# Juice_Rescue_v2_-_hw1_0_2.net
KiCad netlist of a schematic drawn in EAGLE
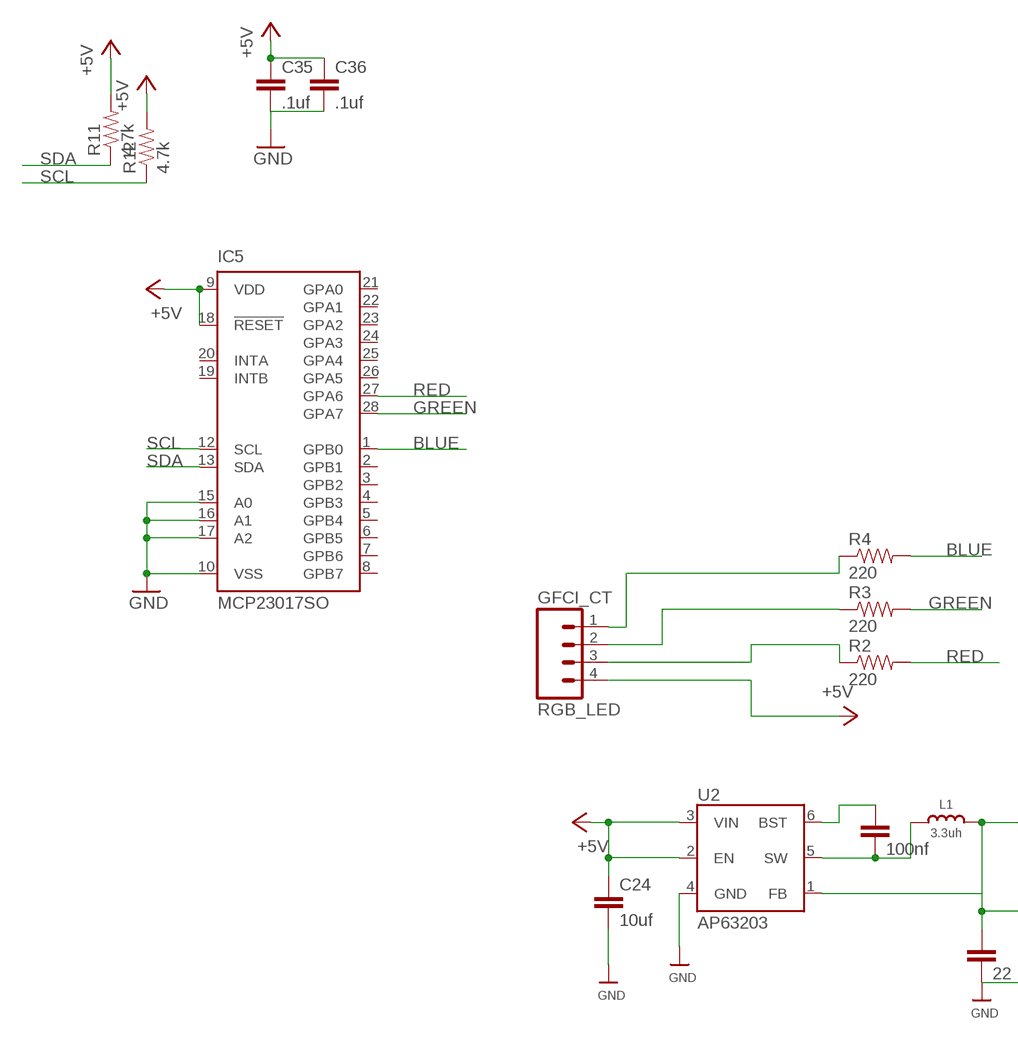
[diagram p0: schematic, sheet 1, part 1 of 2]
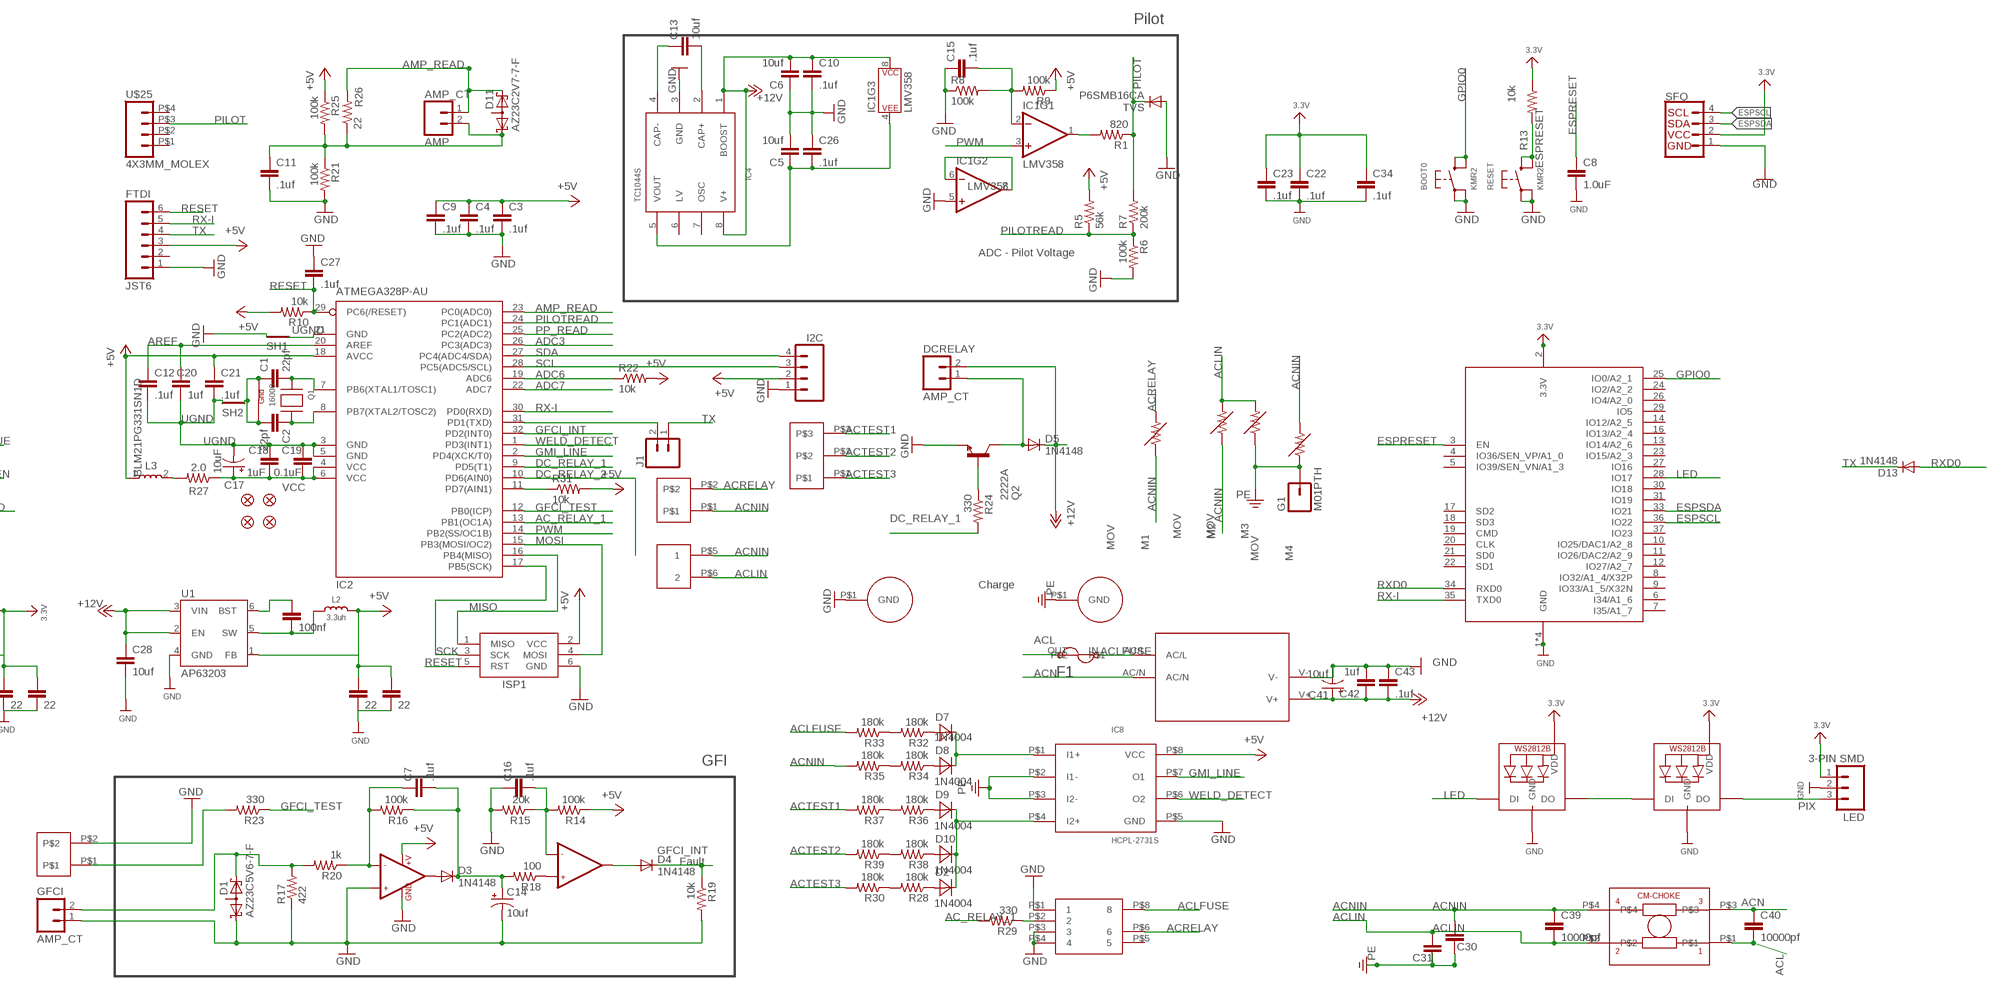
[diagram p1: schematic, sheet 1, part 2 of 2]

(export (version "E")
  (design (tool "Eeschema 10.0.6"))
  (components
    (comp (ref "AC")
      (value "2POS3.96MM")
      (footprint "eagle-import:2POS3.66MM")
      (libsource (lib "eagle-import") (part "2POS3.96MM"))
    )
    (comp (ref "AC_TEST")
      (value "AMPAC3P")
      (footprint "eagle-import:ACAMP3P")
      (libsource (lib "eagle-import") (part "AMPAC3P"))
    )
    (comp (ref "AMP")
      (value "AMP_CT")
      (footprint "eagle-import:MOLEX_2")
      (libsource (lib "eagle-import") (part "MOLEX_2"))
    )
    (comp (ref "BOOT0")
      (value "KMR2")
      (footprint "eagle-import:BTN_KMR2_4.6X2.8")
      (libsource (lib "eagle-import") (part "SWITCH_TACT_SMT4.6X2.8"))
    )
    (comp (ref "C1")
      (value "22pf")
      (footprint "eagle-import:0805")
      (libsource (lib "eagle-import") (part "CAP0805"))
    )
    (comp (ref "C2")
      (value "22pf")
      (footprint "eagle-import:0805")
      (libsource (lib "eagle-import") (part "CAP0805"))
    )
    (comp (ref "C3")
      (value ".1uf")
      (footprint "eagle-import:0805")
      (libsource (lib "eagle-import") (part "CAP0805"))
    )
    (comp (ref "C4")
      (value ".1uf")
      (footprint "eagle-import:0805")
      (libsource (lib "eagle-import") (part "CAP0805"))
    )
    (comp (ref "C5")
      (value "10uf")
      (footprint "eagle-import:0805")
      (libsource (lib "eagle-import") (part "CAP0805"))
    )
    (comp (ref "C6")
      (value "10uf")
      (footprint "eagle-import:0805")
      (libsource (lib "eagle-import") (part "CAP0805"))
    )
    (comp (ref "C7")
      (value ".1uf")
      (footprint "eagle-import:0805")
      (libsource (lib "eagle-import") (part "CAP0805"))
    )
    (comp (ref "C8")
      (value "1.0uF")
      (footprint "eagle-import:0805")
      (libsource (lib "eagle-import") (part "1.0UF-0805-25V-(+80/-20%)"))
    )
    (comp (ref "C9")
      (value ".1uf")
      (footprint "eagle-import:0805")
      (libsource (lib "eagle-import") (part "CAP0805"))
    )
    (comp (ref "C10")
      (value ".1uf")
      (footprint "eagle-import:0805")
      (libsource (lib "eagle-import") (part "CAP0805"))
    )
    (comp (ref "C11")
      (value ".1uf")
      (footprint "eagle-import:0805")
      (libsource (lib "eagle-import") (part "CAP0805"))
    )
    (comp (ref "C12")
      (value ".1uf")
      (footprint "eagle-import:0805")
      (libsource (lib "eagle-import") (part "CAP0805"))
    )
    (comp (ref "C13")
      (value "10uf")
      (footprint "eagle-import:0805")
      (libsource (lib "eagle-import") (part "CAP0805"))
    )
    (comp (ref "C14")
      (value "10uf")
      (footprint "eagle-import:EIA3216")
      (libsource (lib "eagle-import") (part "CAP_POL1206"))
    )
    (comp (ref "C15")
      (value ".1uf")
      (footprint "eagle-import:0805")
      (libsource (lib "eagle-import") (part "CAP0805"))
    )
    (comp (ref "C16")
      (value ".1uf")
      (footprint "eagle-import:0805")
      (libsource (lib "eagle-import") (part "CAP0805"))
    )
    (comp (ref "C17")
      (value "10uF")
      (footprint "eagle-import:0603-POLAR")
      (libsource (lib "eagle-import") (part "10UF-POLAR-0603-6.3V-20%(TANT)"))
    )
    (comp (ref "C18")
      (value "1uF")
      (footprint "eagle-import:0805")
      (libsource (lib "eagle-import") (part "CAP0805"))
    )
    (comp (ref "C19")
      (value "0.1uF")
      (footprint "eagle-import:0805")
      (libsource (lib "eagle-import") (part "CAP0805"))
    )
    (comp (ref "C20")
      (value "1uf")
      (footprint "eagle-import:0805")
      (libsource (lib "eagle-import") (part "CAP0805"))
    )
    (comp (ref "C21")
      (value ".1uf")
      (footprint "eagle-import:0805")
      (libsource (lib "eagle-import") (part "CAP0805"))
    )
    (comp (ref "C22")
      (value ".1uf")
      (footprint "eagle-import:0805")
      (libsource (lib "eagle-import") (part "1.0UF-0805-25V-(+80/-20%)"))
    )
    (comp (ref "C23")
      (value ".1uf")
      (footprint "eagle-import:0805")
      (libsource (lib "eagle-import") (part "1.0UF-0805-25V-(+80/-20%)"))
    )
    (comp (ref "C24")
      (value "10uf")
      (footprint "eagle-import:0805")
      (libsource (lib "eagle-import") (part "1.0UF-0805-25V-(+80/-20%)"))
    )
    (comp (ref "C25")
      (value "22")
      (footprint "eagle-import:0805")
      (libsource (lib "eagle-import") (part "1.0UF-0805-25V-(+80/-20%)"))
    )
    (comp (ref "C26")
      (value ".1uf")
      (footprint "eagle-import:0805")
      (libsource (lib "eagle-import") (part "CAP0805"))
    )
    (comp (ref "C27")
      (value ".1uf")
      (footprint "eagle-import:0805")
      (libsource (lib "eagle-import") (part "CAP0805"))
    )
    (comp (ref "C28")
      (value "10uf")
      (footprint "eagle-import:0805")
      (libsource (lib "eagle-import") (part "1.0UF-0805-25V-(+80/-20%)"))
    )
    (comp (ref "C29")
      (value "22")
      (footprint "eagle-import:0805")
      (libsource (lib "eagle-import") (part "1.0UF-0805-25V-(+80/-20%)"))
    )
    (comp (ref "C30")
      (value "100nf")
      (footprint "eagle-import:0805")
      (libsource (lib "eagle-import") (part "1.0UF-0805-25V-(+80/-20%)"))
    )
    (comp (ref "C31")
      (value "22")
      (footprint "eagle-import:0805")
      (libsource (lib "eagle-import") (part "1.0UF-0805-25V-(+80/-20%)"))
    )
    (comp (ref "C32")
      (value "100nf")
      (footprint "eagle-import:0805")
      (libsource (lib "eagle-import") (part "1.0UF-0805-25V-(+80/-20%)"))
    )
    (comp (ref "C33")
      (value "22")
      (footprint "eagle-import:0805")
      (libsource (lib "eagle-import") (part "1.0UF-0805-25V-(+80/-20%)"))
    )
    (comp (ref "C34")
      (value ".1uf")
      (footprint "eagle-import:0805")
      (libsource (lib "eagle-import") (part "1.0UF-0805-25V-(+80/-20%)"))
    )
    (comp (ref "C35")
      (value ".1uf")
      (footprint "eagle-import:0805")
      (libsource (lib "eagle-import") (part "CAP0805"))
    )
    (comp (ref "C36")
      (value ".1uf")
      (footprint "eagle-import:0805")
      (libsource (lib "eagle-import") (part "CAP0805"))
    )
    (comp (ref "C37")
      (value "1000pf")
      (footprint "eagle-import:DK1E3EA")
      (libsource (lib "eagle-import") (part "DK1"))
    )
    (comp (ref "C39")
      (value "10000pf")
      (footprint "eagle-import:C7.5B4")
      (libsource (lib "eagle-import") (part "C7.5/4"))
    )
    (comp (ref "C40")
      (value "10000pf")
      (footprint "eagle-import:C7.5B4")
      (libsource (lib "eagle-import") (part "C7.5/4"))
    )
    (comp (ref "C41")
      (value "10uf")
      (footprint "eagle-import:EIA3216")
      (libsource (lib "eagle-import") (part "CAP_POL1206"))
    )
    (comp (ref "C42")
      (value "1uf")
      (footprint "eagle-import:0805")
      (libsource (lib "eagle-import") (part "CAP0805"))
    )
    (comp (ref "C43")
      (value ".1uf")
      (footprint "eagle-import:0805")
      (libsource (lib "eagle-import") (part "CAP0805"))
    )
    (comp (ref "CMC")
      (value "RN214-0.3-02-47M")
      (footprint "eagle-import:RN214-0.3-02-47M")
      (libsource (lib "eagle-import") (part "RN214-0.3-02-47M"))
    )
    (comp (ref "D1")
      (value "AZ23C5V6-7-F")
      (footprint "eagle-import:SOT23")
      (libsource (lib "eagle-import") (part "BAS40-06"))
    )
    (comp (ref "D2")
      (value "1N4004")
      (footprint "eagle-import:SMA")
      (libsource (lib "eagle-import") (part "MBRA340T3"))
    )
    (comp (ref "D3")
      (value "1N4148")
      (footprint "eagle-import:SOD123")
      (libsource (lib "eagle-import") (part "DIODE-SOD123"))
    )
    (comp (ref "D4")
      (value "1N4148")
      (footprint "eagle-import:SOD123")
      (libsource (lib "eagle-import") (part "DIODE-SOD123"))
    )
    (comp (ref "D5")
      (value "1N4148")
      (footprint "eagle-import:SOD123")
      (libsource (lib "eagle-import") (part "DIODE-SOD123"))
    )
    (comp (ref "D7")
      (value "1N4004")
      (footprint "eagle-import:SMA")
      (libsource (lib "eagle-import") (part "MBRA340T3"))
    )
    (comp (ref "D8")
      (value "1N4004")
      (footprint "eagle-import:SMA")
      (libsource (lib "eagle-import") (part "MBRA340T3"))
    )
    (comp (ref "D9")
      (value "1N4004")
      (footprint "eagle-import:SMA")
      (libsource (lib "eagle-import") (part "MBRA340T3"))
    )
    (comp (ref "D10")
      (value "1N4004")
      (footprint "eagle-import:SMA")
      (libsource (lib "eagle-import") (part "MBRA340T3"))
    )
    (comp (ref "D11")
      (value "AZ23C2V7-7-F")
      (footprint "eagle-import:SOT23")
      (libsource (lib "eagle-import") (part "BAS40-06"))
    )
    (comp (ref "D13")
      (value "1N4148")
      (footprint "eagle-import:SOD123")
      (libsource (lib "eagle-import") (part "DIODE-SOD123"))
    )
    (comp (ref "DCRELAY")
      (value "AMP_CT")
      (footprint "eagle-import:MOLEX_2")
      (libsource (lib "eagle-import") (part "MOLEX_2"))
    )
    (comp (ref "F1")
      (value "BEL1.6AFUSE")
      (footprint "eagle-import:BELFUSE1A")
      (libsource (lib "eagle-import") (part "BEL1AFUSE"))
    )
    (comp (ref "FID1")
      (value "FIDUCIAL1X2.5")
      (footprint "eagle-import:FIDUCIAL-1X2.5")
      (libsource (lib "eagle-import") (part "FIDUCIAL1X2.5"))
    )
    (comp (ref "FID2")
      (value "FIDUCIAL1X2.5")
      (footprint "eagle-import:FIDUCIAL-1X2.5")
      (libsource (lib "eagle-import") (part "FIDUCIAL1X2.5"))
    )
    (comp (ref "FID3")
      (value "FIDUCIAL1X2.5")
      (footprint "eagle-import:FIDUCIAL-1X2.5")
      (libsource (lib "eagle-import") (part "FIDUCIAL1X2.5"))
    )
    (comp (ref "FID4")
      (value "FIDUCIAL1X2.5")
      (footprint "eagle-import:FIDUCIAL-1X2.5")
      (libsource (lib "eagle-import") (part "FIDUCIAL1X2.5"))
    )
    (comp (ref "FTDI")
      (value "JST6")
      (footprint "eagle-import:JST6")
      (libsource (lib "eagle-import") (part "JST6"))
    )
    (comp (ref "G1")
      (value "M01PTH")
      (footprint "eagle-import:1X01")
      (libsource (lib "eagle-import") (part "M01PTH"))
    )
    (comp (ref "GFCI")
      (value "AMP_CT")
      (footprint "eagle-import:MOLEX_2")
      (libsource (lib "eagle-import") (part "MOLEX_2"))
    )
    (comp (ref "I2C")
      (value "M04JST-PTH-VERT")
      (footprint "eagle-import:JST-4-PTH-VERT")
      (libsource (lib "eagle-import") (part "M04JST-PTH-VERT"))
    )
    (comp (ref "IC1")
      (value "LMV358")
      (footprint "eagle-import:SO08")
      (libsource (lib "eagle-import") (part "LMV358SOIC"))
    )
    (comp (ref "IC2")
      (value "ATMEGA328P-AU")
      (footprint "eagle-import:TQFP32-08")
      (fields (field (name "MPN") "ATMEGA8-16AU"))
      (libsource (lib "eagle-import") (part "MEGA8-AI"))
    )
    (comp (ref "IC3")
      (value "LM358")
      (footprint "eagle-import:SO08")
      (libsource (lib "eagle-import") (part "LMV358"))
    )
    (comp (ref "IC4")
      (value "TC1044S")
      (footprint "eagle-import:SO-8")
      (libsource (lib "eagle-import") (part "TC1044S"))
    )
    (comp (ref "IC5")
      (value "MCP23017SO")
      (footprint "eagle-import:SO28W")
      (libsource (lib "eagle-import") (part "MCP23017SO"))
    )
    (comp (ref "IC7")
      (value "AQH2223")
      (footprint "eagle-import:SIL8")
      (libsource (lib "eagle-import") (part "AQH2223"))
    )
    (comp (ref "IC8")
      (value "HCPL-2731S")
      (footprint "eagle-import:SIL8-2")
      (libsource (lib "eagle-import") (part "HCPL-2731S"))
    )
    (comp (ref "ISP1")
      (value "ISP1")
      (footprint "eagle-import:AVRISP")
      (libsource (lib "eagle-import") (part "AVRISP-6"))
    )
    (comp (ref "J1")
      (value "CONN_02")
      (footprint "eagle-import:1X02")
      (libsource (lib "eagle-import") (part "CONN_02"))
    )
    (comp (ref "L1")
      (value "3.3uh")
      (footprint "eagle-import:MICROBUILDER_INDUCTOR_5X5MM_NR5040_NOTHERMALS")
      (libsource (lib "eagle-import") (part "MICROBUILDER_INDUCTORNR5040"))
    )
    (comp (ref "L2")
      (value "3.3uh")
      (footprint "eagle-import:MICROBUILDER_INDUCTOR_5X5MM_NR5040_NOTHERMALS")
      (libsource (lib "eagle-import") (part "MICROBUILDER_INDUCTORNR5040"))
    )
    (comp (ref "L3")
      (value "BLM21PG331SN1D")
      (footprint "eagle-import:INDC2012X87")
      (fields (field (name "MF") "Murata"))
      (libsource (lib "eagle-import") (part "BLM21PG331SN1D"))
    )
    (comp (ref "LED")
      (value "3-PIN SMD")
      (footprint "eagle-import:JST-3-SMD")
      (libsource (lib "eagle-import") (part "M03JST-SMD"))
    )
    (comp (ref "LED1")
      (value "WS2812B3535")
      (footprint "eagle-import:LED3535")
      (libsource (lib "eagle-import") (part "WS2812B3535"))
    )
    (comp (ref "LED2")
      (value "WS2812B3535")
      (footprint "eagle-import:LED3535")
      (libsource (lib "eagle-import") (part "WS2812B3535"))
    )
    (comp (ref "M1")
      (value "MOV")
      (footprint "eagle-import:MOV")
      (libsource (lib "eagle-import") (part "MOV"))
    )
    (comp (ref "M2")
      (value "MOV")
      (footprint "eagle-import:MOV")
      (libsource (lib "eagle-import") (part "MOV"))
    )
    (comp (ref "M3")
      (value "MOV")
      (footprint "eagle-import:MOV")
      (libsource (lib "eagle-import") (part "MOV"))
    )
    (comp (ref "M4")
      (value "MOV")
      (footprint "eagle-import:MOV")
      (libsource (lib "eagle-import") (part "MOV"))
    )
    (comp (ref "PS1")
      (value "IRM-10-5")
      (footprint "eagle-import:IRM-10-5")
      (libsource (lib "eagle-import") (part "IRM-10-5"))
    )
    (comp (ref "Q1")
      (value "16000")
      (footprint "eagle-import:NX3225")
      (libsource (lib "eagle-import") (part "XTAL-4-3225"))
    )
    (comp (ref "Q2")
      (value "2222A")
      (footprint "eagle-import:SOT23")
      (libsource (lib "eagle-import") (part "BCX70SMD"))
    )
    (comp (ref "R1")
      (value "820")
      (footprint "eagle-import:0805")
      (libsource (lib "eagle-import") (part "RESISTOR0805-RES"))
    )
    (comp (ref "R2")
      (value "220")
      (footprint "eagle-import:0805")
      (libsource (lib "eagle-import") (part "RESISTOR0805-RES"))
    )
    (comp (ref "R3")
      (value "220")
      (footprint "eagle-import:0805")
      (libsource (lib "eagle-import") (part "RESISTOR0805-RES"))
    )
    (comp (ref "R4")
      (value "220")
      (footprint "eagle-import:0805")
      (libsource (lib "eagle-import") (part "RESISTOR0805-RES"))
    )
    (comp (ref "R5")
      (value "56k")
      (footprint "eagle-import:0805")
      (libsource (lib "eagle-import") (part "RESISTOR0805-RES"))
    )
    (comp (ref "R6")
      (value "100k")
      (footprint "eagle-import:0805")
      (libsource (lib "eagle-import") (part "RESISTOR0805-RES"))
    )
    (comp (ref "R7")
      (value "200k")
      (footprint "eagle-import:0805")
      (libsource (lib "eagle-import") (part "RESISTOR0805-RES"))
    )
    (comp (ref "R8")
      (value "100k")
      (footprint "eagle-import:0805")
      (libsource (lib "eagle-import") (part "RESISTOR0805-RES"))
    )
    (comp (ref "R9")
      (value "100k")
      (footprint "eagle-import:0805")
      (libsource (lib "eagle-import") (part "RESISTOR0805-RES"))
    )
    (comp (ref "R10")
      (value "10k")
      (footprint "eagle-import:0805")
      (libsource (lib "eagle-import") (part "RESISTOR0805-RES"))
    )
    (comp (ref "R11")
      (value "4.7k")
      (footprint "eagle-import:0805")
      (libsource (lib "eagle-import") (part "RESISTOR0805-RES"))
    )
    (comp (ref "R12")
      (value "4.7k")
      (footprint "eagle-import:0805")
      (libsource (lib "eagle-import") (part "RESISTOR0805-RES"))
    )
    (comp (ref "R13")
      (value "10k")
      (footprint "eagle-import:0805")
      (libsource (lib "eagle-import") (part "RESISTOR0805"))
    )
    (comp (ref "R14")
      (value "100k")
      (footprint "eagle-import:0805")
      (libsource (lib "eagle-import") (part "RESISTOR0805-RES"))
    )
    (comp (ref "R15")
      (value "20k")
      (footprint "eagle-import:0805")
      (libsource (lib "eagle-import") (part "RESISTOR0805-RES"))
    )
    (comp (ref "R16")
      (value "100k")
      (footprint "eagle-import:0805")
      (libsource (lib "eagle-import") (part "RESISTOR0805-RES"))
    )
    (comp (ref "R17")
      (value "422")
      (footprint "eagle-import:0805")
      (libsource (lib "eagle-import") (part "RESISTOR0805-RES"))
    )
    (comp (ref "R18")
      (value "100")
      (footprint "eagle-import:0805")
      (libsource (lib "eagle-import") (part "RESISTOR0805-RES"))
    )
    (comp (ref "R19")
      (value "10k")
      (footprint "eagle-import:0805")
      (libsource (lib "eagle-import") (part "RESISTOR0805-RES"))
    )
    (comp (ref "R20")
      (value "1k")
      (footprint "eagle-import:0805")
      (libsource (lib "eagle-import") (part "RESISTOR0805-RES"))
    )
    (comp (ref "R21")
      (value "100k")
      (footprint "eagle-import:0805")
      (libsource (lib "eagle-import") (part "RESISTOR0805-RES"))
    )
    (comp (ref "R22")
      (value "10k")
      (footprint "eagle-import:0805")
      (libsource (lib "eagle-import") (part "RESISTOR0805-RES"))
    )
    (comp (ref "R23")
      (value "330")
      (footprint "eagle-import:0805")
      (libsource (lib "eagle-import") (part "RESISTOR0805-RES"))
    )
    (comp (ref "R24")
      (value "330")
      (footprint "eagle-import:0805")
      (libsource (lib "eagle-import") (part "RESISTOR0805-RES"))
    )
    (comp (ref "R25")
      (value "100k")
      (footprint "eagle-import:0805")
      (libsource (lib "eagle-import") (part "RESISTOR0805-RES"))
    )
    (comp (ref "R26")
      (value "22")
      (footprint "eagle-import:R1206")
      (libsource (lib "eagle-import") (part "R-US_R1206"))
    )
    (comp (ref "R27")
      (value "2.0")
      (footprint "eagle-import:0805")
      (libsource (lib "eagle-import") (part "RESISTOR0805-RES"))
    )
    (comp (ref "R28")
      (value "180k")
      (footprint "eagle-import:1210")
      (libsource (lib "eagle-import") (part "0.1OHM-1/2W-1%(1210)"))
    )
    (comp (ref "R29")
      (value "330")
      (footprint "eagle-import:0805")
      (libsource (lib "eagle-import") (part "RESISTOR0805-RES"))
    )
    (comp (ref "R30")
      (value "180k")
      (footprint "eagle-import:1210")
      (libsource (lib "eagle-import") (part "0.1OHM-1/2W-1%(1210)"))
    )
    (comp (ref "R31")
      (value "10k")
      (footprint "eagle-import:0805")
      (libsource (lib "eagle-import") (part "RESISTOR0805-RES"))
    )
    (comp (ref "R32")
      (value "180k")
      (footprint "eagle-import:1210")
      (libsource (lib "eagle-import") (part "0.1OHM-1/2W-1%(1210)"))
    )
    (comp (ref "R33")
      (value "180k")
      (footprint "eagle-import:1210")
      (libsource (lib "eagle-import") (part "0.1OHM-1/2W-1%(1210)"))
    )
    (comp (ref "R34")
      (value "180k")
      (footprint "eagle-import:1210")
      (libsource (lib "eagle-import") (part "0.1OHM-1/2W-1%(1210)"))
    )
    (comp (ref "R35")
      (value "180k")
      (footprint "eagle-import:1210")
      (libsource (lib "eagle-import") (part "0.1OHM-1/2W-1%(1210)"))
    )
    (comp (ref "R36")
      (value "180k")
      (footprint "eagle-import:1210")
      (libsource (lib "eagle-import") (part "0.1OHM-1/2W-1%(1210)"))
    )
    (comp (ref "R37")
      (value "180k")
      (footprint "eagle-import:1210")
      (libsource (lib "eagle-import") (part "0.1OHM-1/2W-1%(1210)"))
    )
    (comp (ref "R38")
      (value "180k")
      (footprint "eagle-import:1210")
      (libsource (lib "eagle-import") (part "0.1OHM-1/2W-1%(1210)"))
    )
    (comp (ref "R39")
      (value "180k")
      (footprint "eagle-import:1210")
      (libsource (lib "eagle-import") (part "0.1OHM-1/2W-1%(1210)"))
    )
    (comp (ref "RESET")
      (value "KMR2")
      (footprint "eagle-import:BTN_KMR2_4.6X2.8")
      (libsource (lib "eagle-import") (part "SWITCH_TACT_SMT4.6X2.8"))
    )
    (comp (ref "RF1")
      (value "1000pf")
      (footprint "eagle-import:DK1E3EA")
      (libsource (lib "eagle-import") (part "DK1"))
    )
    (comp (ref "RGB_LED")
      (value "GFCI_CT")
      (footprint "eagle-import:GFCI_4")
      (libsource (lib "eagle-import") (part "GFCI_4"))
    )
    (comp (ref "SFQ")
      (value "QWIIC_CONNECTORJS-1MM")
      (footprint "eagle-import:JST04_1MM_RA")
      (libsource (lib "eagle-import") (part "QWIIC_CONNECTORJS-1MM"))
    )
    (comp (ref "SH1")
      (value "SHORT-HT5")
      (footprint "eagle-import:SHORT_TOP-50")
      (libsource (lib "eagle-import") (part "SHORT-HT5"))
    )
    (comp (ref "SH2")
      (value "SHORT-HT5")
      (footprint "eagle-import:SHORT_TOP-50")
      (libsource (lib "eagle-import") (part "SHORT-HT5"))
    )
    (comp (ref "TEST_COIL")
      (value "2X4MM")
      (footprint "eagle-import:2X4MM")
      (libsource (lib "eagle-import") (part "2X4MM"))
    )
    (comp (ref "TVS")
      (value "P6SMB16CA")
      (footprint "eagle-import:SMB")
      (libsource (lib "eagle-import") (part "DIODE-SMB"))
    )
    (comp (ref "U$3")
      (value "HOLE")
      (footprint "eagle-import:HOLE")
      (libsource (lib "eagle-import") (part "HOLE"))
    )
    (comp (ref "U$8")
      (value "AMPAC")
      (footprint "eagle-import:AMPAC")
      (libsource (lib "eagle-import") (part "AMPAC"))
    )
    (comp (ref "U$9")
      (value "HOLE")
      (footprint "eagle-import:HOLE")
      (libsource (lib "eagle-import") (part "HOLE"))
    )
    (comp (ref "U$25")
      (value "4X3MM_MOLEX")
      (footprint "eagle-import:4X3MM_MOLEX")
      (libsource (lib "eagle-import") (part "4X3MM_MOLEX"))
    )
    (comp (ref "U1")
      (value "AP63203")
      (footprint "eagle-import:SOT23-6")
      (libsource (lib "eagle-import") (part "AP63203"))
    )
    (comp (ref "U2")
      (value "AP63203")
      (footprint "eagle-import:SOT23-6")
      (libsource (lib "eagle-import") (part "AP63203"))
    )
    (comp (ref "X2")
      (value "ESP32-WROOM-32")
      (footprint "eagle-import:WROOM32_SKINNY")
      (libsource (lib "eagle-import") (part "ESP32_WROOM32_SKINNY"))
    )
  )
  (nets
    (net (code "1") (name "+5V") (class "Default")
      (node (ref "C21") (pin "1") (pinfunction "1_1") (pintype "passive"))
      (node (ref "C24") (pin "1") (pinfunction "1_1") (pintype "passive"))
      (node (ref "C29") (pin "1") (pinfunction "1_1") (pintype "passive"))
      (node (ref "C3") (pin "1") (pinfunction "1_1") (pintype "passive"))
      (node (ref "C33") (pin "1") (pinfunction "1_1") (pintype "passive"))
      (node (ref "C35") (pin "1") (pinfunction "1_1") (pintype "passive"))
      (node (ref "C36") (pin "1") (pinfunction "1_1") (pintype "passive"))
      (node (ref "C4") (pin "1") (pinfunction "1_1") (pintype "passive"))
      (node (ref "C9") (pin "1") (pinfunction "1_1") (pintype "passive"))
      (node (ref "FTDI") (pin "3") (pinfunction "3_3") (pintype "passive"))
      (node (ref "I2C") (pin "2") (pinfunction "2_2") (pintype "passive"))
      (node (ref "IC2") (pin "18") (pinfunction "AVCC_18") (pintype "power_in"))
      (node (ref "IC3") (pin "8") (pinfunction "+V_8") (pintype "power_in"))
      (node (ref "IC5") (pin "18") (pinfunction "~{RESET}_18") (pintype "input"))
      (node (ref "IC5") (pin "9") (pinfunction "VDD_9") (pintype "power_in"))
      (node (ref "IC8") (pin "P$8") (pinfunction "VCC_P$8") (pintype "bidirectional"))
      (node (ref "ISP1") (pin "2") (pinfunction "VCC_2") (pintype "power_in"))
      (node (ref "L2") (pin "P$2") (pinfunction "2_P$2") (pintype "passive"))
      (node (ref "L3") (pin "1") (pinfunction "1_1") (pintype "passive"))
      (node (ref "R10") (pin "2") (pinfunction "2_2") (pintype "passive"))
      (node (ref "R11") (pin "2") (pinfunction "2_2") (pintype "passive"))
      (node (ref "R12") (pin "2") (pinfunction "2_2") (pintype "passive"))
      (node (ref "R14") (pin "1") (pinfunction "1_1") (pintype "passive"))
      (node (ref "R22") (pin "2") (pinfunction "2_2") (pintype "passive"))
      (node (ref "R25") (pin "1") (pinfunction "1_1") (pintype "passive"))
      (node (ref "R31") (pin "2") (pinfunction "2_2") (pintype "passive"))
      (node (ref "R5") (pin "2") (pinfunction "2_2") (pintype "passive"))
      (node (ref "R9") (pin "1") (pinfunction "1_1") (pintype "passive"))
      (node (ref "RGB_LED") (pin "4") (pinfunction "4_4") (pintype "passive"))
      (node (ref "U1") (pin "1") (pinfunction "FB_1") (pintype "bidirectional"))
      (node (ref "U2") (pin "2") (pinfunction "EN_2") (pintype "bidirectional"))
      (node (ref "U2") (pin "3") (pinfunction "VIN_3") (pintype "bidirectional"))
    )
    (net (code "2") (name "+12V") (class "Default")
      (node (ref "C10") (pin "1") (pinfunction "1_1") (pintype "passive"))
      (node (ref "C28") (pin "1") (pinfunction "1_1") (pintype "passive"))
      (node (ref "C41") (pin "A") (pinfunction "+_A") (pintype "passive"))
      (node (ref "C42") (pin "1") (pinfunction "1_1") (pintype "passive"))
      (node (ref "C43") (pin "2") (pinfunction "2_2") (pintype "passive"))
      (node (ref "C6") (pin "2") (pinfunction "2_2") (pintype "passive"))
      (node (ref "D5") (pin "C") (pinfunction "C_C") (pintype "passive"))
      (node (ref "DCRELAY") (pin "2") (pinfunction "2_2") (pintype "passive"))
      (node (ref "IC1") (pin "8") (pinfunction "P$V+_8") (pintype "bidirectional"))
      (node (ref "IC4") (pin "1") (pinfunction "BOOST_1") (pintype "bidirectional"))
      (node (ref "IC4") (pin "8") (pinfunction "V+_8") (pintype "bidirectional"))
      (node (ref "PS1") (pin "V+") (pinfunction "V+_V+") (pintype "bidirectional"))
      (node (ref "U1") (pin "2") (pinfunction "EN_2") (pintype "bidirectional"))
      (node (ref "U1") (pin "3") (pinfunction "VIN_3") (pintype "bidirectional"))
    )
    (net (code "3") (name "/ACL") (class "Default")
      (node (ref "C40") (pin "2") (pinfunction "2_2") (pintype "passive"))
      (node (ref "CMC") (pin "P$1") (pinfunction "P$1_P$1") (pintype "bidirectional"))
      (node (ref "F1") (pin "OUT") (pinfunction "P$1_OUT") (pintype "bidirectional"))
    )
    (net (code "4") (name "/ACLFUSE") (class "Default")
      (node (ref "F1") (pin "IN") (pinfunction "P$2_IN") (pintype "bidirectional"))
      (node (ref "IC7") (pin "P$8") (pinfunction "8_P$8") (pintype "bidirectional"))
      (node (ref "PS1") (pin "AC/L") (pinfunction "AC/L_AC/L") (pintype "bidirectional"))
      (node (ref "R33") (pin "2") (pinfunction "2_2") (pintype "passive"))
    )
    (net (code "5") (name "/ACLIN") (class "Default")
      (node (ref "AC") (pin "P$6") (pinfunction "2_P$6") (pintype "bidirectional"))
      (node (ref "C39") (pin "2") (pinfunction "2_2") (pintype "passive"))
      (node (ref "CMC") (pin "P$2") (pinfunction "P$2_P$2") (pintype "bidirectional"))
      (node (ref "M2") (pin "P$2") (pinfunction "2_P$2") (pintype "passive"))
      (node (ref "M3") (pin "P$2") (pinfunction "2_P$2") (pintype "passive"))
      (node (ref "RF1") (pin "P$2") (pinfunction "2_P$2") (pintype "passive"))
    )
    (net (code "6") (name "/ACN") (class "Default")
      (node (ref "C40") (pin "1") (pinfunction "1_1") (pintype "passive"))
      (node (ref "CMC") (pin "P$3") (pinfunction "P$3_P$3") (pintype "bidirectional"))
      (node (ref "PS1") (pin "AC/N") (pinfunction "AC/N_AC/N") (pintype "bidirectional"))
    )
    (net (code "7") (name "/ACNIN") (class "Default")
      (node (ref "AC") (pin "P$5") (pinfunction "1_P$5") (pintype "bidirectional"))
      (node (ref "C37") (pin "P$2") (pinfunction "2_P$2") (pintype "passive"))
      (node (ref "C39") (pin "1") (pinfunction "1_1") (pintype "passive"))
      (node (ref "CMC") (pin "P$4") (pinfunction "P$4_P$4") (pintype "bidirectional"))
      (node (ref "M1") (pin "P$1") (pinfunction "1_P$1") (pintype "passive"))
      (node (ref "M2") (pin "P$1") (pinfunction "1_P$1") (pintype "passive"))
      (node (ref "M4") (pin "P$2") (pinfunction "2_P$2") (pintype "passive"))
      (node (ref "R35") (pin "2") (pinfunction "2_2") (pintype "passive"))
      (node (ref "U$8") (pin "P$1") (pinfunction "P$1_P$1") (pintype "bidirectional"))
    )
    (net (code "8") (name "/ACRELAY") (class "Default")
      (node (ref "IC7") (pin "P$6") (pinfunction "6_P$6") (pintype "bidirectional"))
      (node (ref "M1") (pin "P$2") (pinfunction "2_P$2") (pintype "passive"))
      (node (ref "U$8") (pin "P$2") (pinfunction "P$2_P$2") (pintype "bidirectional"))
    )
    (net (code "9") (name "/ACTEST1") (class "Default")
      (node (ref "AC_TEST") (pin "P$3") (pinfunction "P$3_P$3") (pintype "bidirectional"))
      (node (ref "R37") (pin "2") (pinfunction "2_2") (pintype "passive"))
    )
    (net (code "10") (name "/ACTEST2") (class "Default")
      (node (ref "AC_TEST") (pin "P$2") (pinfunction "P$2_P$2") (pintype "bidirectional"))
      (node (ref "R39") (pin "2") (pinfunction "2_2") (pintype "passive"))
    )
    (net (code "11") (name "/ACTEST3") (class "Default")
      (node (ref "AC_TEST") (pin "P$1") (pinfunction "P$1_P$1") (pintype "bidirectional"))
      (node (ref "R30") (pin "2") (pinfunction "2_2") (pintype "passive"))
    )
    (net (code "12") (name "/AC_RELAY_1") (class "Default")
      (node (ref "IC2") (pin "13") (pinfunction "PB1(OC1A)_13") (pintype "bidirectional"))
      (node (ref "R29") (pin "2") (pinfunction "2_2") (pintype "passive"))
    )
    (net (code "13") (name "/ADC3") (class "Default")
      (node (ref "IC2") (pin "26") (pinfunction "PC3(ADC3)_26") (pintype "bidirectional"))
    )
    (net (code "14") (name "/ADC6") (class "Default")
      (node (ref "IC2") (pin "19") (pinfunction "ADC6_19") (pintype "bidirectional"))
      (node (ref "R22") (pin "1") (pinfunction "1_1") (pintype "passive"))
    )
    (net (code "15") (name "/ADC7") (class "Default")
      (node (ref "IC2") (pin "22") (pinfunction "ADC7_22") (pintype "bidirectional"))
    )
    (net (code "16") (name "/AMP_READ") (class "Default")
      (node (ref "AMP") (pin "1") (pinfunction "1_1") (pintype "passive"))
      (node (ref "D11") (pin "2") (pinfunction "K2_2") (pintype "passive"))
      (node (ref "IC2") (pin "23") (pinfunction "PC0(ADC0)_23") (pintype "bidirectional"))
      (node (ref "R26") (pin "2") (pinfunction "2_2") (pintype "passive"))
    )
    (net (code "17") (name "/AREF") (class "Default")
      (node (ref "C12") (pin "1") (pinfunction "1_1") (pintype "passive"))
      (node (ref "C20") (pin "1") (pinfunction "1_1") (pintype "passive"))
      (node (ref "IC2") (pin "20") (pinfunction "AREF_20") (pintype "passive"))
    )
    (net (code "18") (name "/BLUE") (class "Default")
      (node (ref "IC5") (pin "1") (pinfunction "GPB0_1") (pintype "bidirectional"))
      (node (ref "R4") (pin "2") (pinfunction "2_2") (pintype "passive"))
    )
    (net (code "19") (name "/DC_RELAY_1") (class "Default")
      (node (ref "IC2") (pin "9") (pinfunction "PD5(T1)_9") (pintype "bidirectional"))
      (node (ref "R24") (pin "2") (pinfunction "2_2") (pintype "passive"))
    )
    (net (code "20") (name "/DC_RELAY_2") (class "Default")
      (node (ref "IC2") (pin "10") (pinfunction "PD6(AIN0)_10") (pintype "bidirectional"))
    )
    (net (code "21") (name "/ESPRESET") (class "Default")
      (node (ref "C8") (pin "1") (pinfunction "1_1") (pintype "passive"))
      (node (ref "R13") (pin "2") (pinfunction "2_2") (pintype "passive"))
      (node (ref "RESET") (pin "B") (pinfunction "S_B") (pintype "passive"))
      (node (ref "RESET") (pin "B'") (pinfunction "S1_B'") (pintype "passive"))
      (node (ref "X2") (pin "3") (pinfunction "EN_3") (pintype "input"))
    )
    (net (code "22") (name "/GFCI_INT") (class "Default")
      (node (ref "D4") (pin "C") (pinfunction "C_C") (pintype "passive"))
      (node (ref "IC2") (pin "32") (pinfunction "PD2(INT0)_32") (pintype "bidirectional"))
      (node (ref "R19") (pin "1") (pinfunction "1_1") (pintype "passive"))
    )
    (net (code "23") (name "/GFCI_TEST") (class "Default")
      (node (ref "IC2") (pin "12") (pinfunction "PB0(ICP)_12") (pintype "bidirectional"))
      (node (ref "R23") (pin "1") (pinfunction "1_1") (pintype "passive"))
    )
    (net (code "24") (name "/GMI_LINE") (class "Default")
      (node (ref "IC2") (pin "2") (pinfunction "PD4(XCK/T0)_2") (pintype "bidirectional"))
      (node (ref "IC8") (pin "P$7") (pinfunction "O1_P$7") (pintype "bidirectional"))
    )
    (net (code "25") (name "/GPIO0") (class "Default")
      (node (ref "BOOT0") (pin "B") (pinfunction "S_B") (pintype "passive"))
      (node (ref "BOOT0") (pin "B'") (pinfunction "S1_B'") (pintype "passive"))
      (node (ref "X2") (pin "25") (pinfunction "IO0/A2_1_25") (pintype "bidirectional"))
    )
    (net (code "26") (name "/GREEN") (class "Default")
      (node (ref "IC5") (pin "28") (pinfunction "GPA7_28") (pintype "bidirectional"))
      (node (ref "R3") (pin "2") (pinfunction "2_2") (pintype "passive"))
    )
    (net (code "27") (name "/LED") (class "Default")
      (node (ref "LED1") (pin "1") (pinfunction "DI_1") (pintype "input"))
      (node (ref "X2") (pin "28") (pinfunction "IO17_28") (pintype "bidirectional"))
    )
    (net (code "28") (name "/MISO") (class "Default")
      (node (ref "IC2") (pin "16") (pinfunction "PB4(MISO)_16") (pintype "bidirectional"))
      (node (ref "ISP1") (pin "1") (pinfunction "MISO_1") (pintype "input"))
    )
    (net (code "29") (name "/MOSI") (class "Default")
      (node (ref "IC2") (pin "15") (pinfunction "PB3(MOSI/OC2)_15") (pintype "bidirectional"))
      (node (ref "ISP1") (pin "4") (pinfunction "MOSI_4") (pintype "output"))
    )
    (net (code "30") (name "/PILOT") (class "Default")
      (node (ref "R1") (pin "1") (pinfunction "1_1") (pintype "passive"))
      (node (ref "R7") (pin "2") (pinfunction "2_2") (pintype "passive"))
      (node (ref "TVS") (pin "C") (pinfunction "C_C") (pintype "passive"))
      (node (ref "U$25") (pin "P$3") (pinfunction "3_P$3") (pintype "passive"))
    )
    (net (code "31") (name "/PILOTREAD") (class "Default")
      (node (ref "IC2") (pin "24") (pinfunction "PC1(ADC1)_24") (pintype "bidirectional"))
      (node (ref "R5") (pin "1") (pinfunction "1_1") (pintype "passive"))
      (node (ref "R6") (pin "1") (pinfunction "1_1") (pintype "passive"))
      (node (ref "R7") (pin "1") (pinfunction "1_1") (pintype "passive"))
    )
    (net (code "32") (name "/PIX") (class "Default")
      (node (ref "LED") (pin "3") (pinfunction "3_3") (pintype "passive"))
      (node (ref "LED2") (pin "3") (pinfunction "DO_3") (pintype "output"))
    )
    (net (code "33") (name "/PP_READ") (class "Default")
      (node (ref "IC2") (pin "25") (pinfunction "PC2(ADC2)_25") (pintype "bidirectional"))
    )
    (net (code "34") (name "/PWM") (class "Default")
      (node (ref "IC1") (pin "3") (pinfunction "+IN_3") (pintype "input"))
      (node (ref "IC2") (pin "14") (pinfunction "PB2(SS/OC1B)_14") (pintype "bidirectional"))
    )
    (net (code "35") (name "/RED") (class "Default")
      (node (ref "IC5") (pin "27") (pinfunction "GPA6_27") (pintype "bidirectional"))
      (node (ref "R2") (pin "2") (pinfunction "2_2") (pintype "passive"))
    )
    (net (code "36") (name "/RESET") (class "Default")
      (node (ref "C27") (pin "2") (pinfunction "2_2") (pintype "passive"))
      (node (ref "FTDI") (pin "6") (pinfunction "6_6") (pintype "passive"))
      (node (ref "IC2") (pin "29") (pinfunction "PC6(/RESET)_29") (pintype "bidirectional"))
      (node (ref "ISP1") (pin "5") (pinfunction "RST_5") (pintype "output"))
      (node (ref "R10") (pin "1") (pinfunction "1_1") (pintype "passive"))
    )
    (net (code "37") (name "/RX-I") (class "Default")
      (node (ref "FTDI") (pin "5") (pinfunction "5_5") (pintype "passive"))
      (node (ref "IC2") (pin "30") (pinfunction "PD0(RXD)_30") (pintype "bidirectional"))
      (node (ref "X2") (pin "35") (pinfunction "TXD0_35") (pintype "output"))
    )
    (net (code "38") (name "/RXD0") (class "Default")
      (node (ref "D13") (pin "A") (pinfunction "A_A") (pintype "passive"))
      (node (ref "X2") (pin "34") (pinfunction "RXD0_34") (pintype "input"))
    )
    (net (code "39") (name "/SCK") (class "Default")
      (node (ref "IC2") (pin "17") (pinfunction "PB5(SCK)_17") (pintype "bidirectional"))
      (node (ref "ISP1") (pin "3") (pinfunction "SCK_3") (pintype "output"))
    )
    (net (code "40") (name "/SCL") (class "Default")
      (node (ref "I2C") (pin "3") (pinfunction "3_3") (pintype "passive"))
      (node (ref "IC2") (pin "28") (pinfunction "PC5(ADC5/SCL)_28") (pintype "bidirectional"))
      (node (ref "IC5") (pin "12") (pinfunction "SCL_12") (pintype "input"))
      (node (ref "R12") (pin "1") (pinfunction "1_1") (pintype "passive"))
    )
    (net (code "41") (name "/SDA") (class "Default")
      (node (ref "I2C") (pin "4") (pinfunction "4_4") (pintype "passive"))
      (node (ref "IC2") (pin "27") (pinfunction "PC4(ADC4/SDA)_27") (pintype "bidirectional"))
      (node (ref "IC5") (pin "13") (pinfunction "SDA_13") (pintype "bidirectional"))
      (node (ref "R11") (pin "1") (pinfunction "1_1") (pintype "passive"))
    )
    (net (code "42") (name "/TX") (class "Default")
      (node (ref "D13") (pin "C") (pinfunction "C_C") (pintype "passive"))
      (node (ref "FTDI") (pin "4") (pinfunction "4_4") (pintype "passive"))
      (node (ref "J1") (pin "1") (pinfunction "1_1") (pintype "passive"))
    )
    (net (code "43") (name "/UGND") (class "Default")
      (node (ref "C12") (pin "2") (pinfunction "2_2") (pintype "passive"))
      (node (ref "C17") (pin "-") (pinfunction "-_-") (pintype "passive"))
      (node (ref "C18") (pin "1") (pinfunction "1_1") (pintype "passive"))
      (node (ref "C19") (pin "1") (pinfunction "1_1") (pintype "passive"))
      (node (ref "C20") (pin "2") (pinfunction "2_2") (pintype "passive"))
      (node (ref "C21") (pin "2") (pinfunction "2_2") (pintype "passive"))
      (node (ref "IC2") (pin "21") (pinfunction "GND_21") (pintype "power_in"))
      (node (ref "IC2") (pin "3") (pinfunction "GND_3") (pintype "power_in"))
      (node (ref "IC2") (pin "5") (pinfunction "GND_5") (pintype "power_in"))
      (node (ref "SH1") (pin "1") (pinfunction "P$1_1") (pintype "bidirectional"))
      (node (ref "SH2") (pin "2") (pinfunction "P$2_2") (pintype "bidirectional"))
    )
    (net (code "44") (name "/VCC") (class "Default")
      (node (ref "C17") (pin "+") (pinfunction "+_+") (pintype "passive"))
      (node (ref "C18") (pin "2") (pinfunction "2_2") (pintype "passive"))
      (node (ref "C19") (pin "2") (pinfunction "2_2") (pintype "passive"))
      (node (ref "IC2") (pin "4") (pinfunction "VCC_4") (pintype "power_in"))
      (node (ref "IC2") (pin "6") (pinfunction "VCC_6") (pintype "power_in"))
      (node (ref "R27") (pin "1") (pinfunction "1_1") (pintype "passive"))
    )
    (net (code "45") (name "/WELD_DETECT") (class "Default")
      (node (ref "IC2") (pin "1") (pinfunction "PD3(INT1)_1") (pintype "bidirectional"))
      (node (ref "IC8") (pin "P$6") (pinfunction "O2_P$6") (pintype "bidirectional"))
    )
    (net (code "46") (name "3.3V") (class "Default")
      (node (ref "C22") (pin "1") (pinfunction "1_1") (pintype "passive"))
      (node (ref "C23") (pin "1") (pinfunction "1_1") (pintype "passive"))
      (node (ref "C25") (pin "1") (pinfunction "1_1") (pintype "passive"))
      (node (ref "C31") (pin "1") (pinfunction "1_1") (pintype "passive"))
      (node (ref "C34") (pin "1") (pinfunction "1_1") (pintype "passive"))
      (node (ref "L1") (pin "P$2") (pinfunction "2_P$2") (pintype "passive"))
      (node (ref "LED") (pin "1") (pinfunction "1_1") (pintype "passive"))
      (node (ref "LED1") (pin "2") (pinfunction "VDD_2") (pintype "power_in"))
      (node (ref "LED2") (pin "2") (pinfunction "VDD_2") (pintype "power_in"))
      (node (ref "R13") (pin "1") (pinfunction "1_1") (pintype "passive"))
      (node (ref "SFQ") (pin "2") (pinfunction "2_2") (pintype "power_in"))
      (node (ref "U2") (pin "1") (pinfunction "FB_1") (pintype "bidirectional"))
      (node (ref "X2") (pin "2") (pinfunction "3.3V_2") (pintype "passive"))
    )
    (net (code "47") (name "ESPSCL") (class "Default")
      (node (ref "SFQ") (pin "4") (pinfunction "4_4") (pintype "passive"))
      (node (ref "X2") (pin "36") (pinfunction "IO22_36") (pintype "bidirectional"))
    )
    (net (code "48") (name "ESPSDA") (class "Default")
      (node (ref "SFQ") (pin "3") (pinfunction "3_3") (pintype "passive"))
      (node (ref "X2") (pin "33") (pinfunction "IO21_33") (pintype "bidirectional"))
    )
    (net (code "49") (name "GND") (class "Default")
      (node (ref "BOOT0") (pin "A") (pinfunction "P_A") (pintype "passive"))
      (node (ref "BOOT0") (pin "A'") (pinfunction "P1_A'") (pintype "passive"))
      (node (ref "C10") (pin "2") (pinfunction "2_2") (pintype "passive"))
      (node (ref "C11") (pin "2") (pinfunction "2_2") (pintype "passive"))
      (node (ref "C14") (pin "C") (pinfunction "-_C") (pintype "passive"))
      (node (ref "C15") (pin "1") (pinfunction "1_1") (pintype "passive"))
      (node (ref "C16") (pin "1") (pinfunction "1_1") (pintype "passive"))
      (node (ref "C22") (pin "2") (pinfunction "2_2") (pintype "passive"))
      (node (ref "C23") (pin "2") (pinfunction "2_2") (pintype "passive"))
      (node (ref "C24") (pin "2") (pinfunction "2_2") (pintype "passive"))
      (node (ref "C25") (pin "2") (pinfunction "2_2") (pintype "passive"))
      (node (ref "C26") (pin "1") (pinfunction "1_1") (pintype "passive"))
      (node (ref "C27") (pin "1") (pinfunction "1_1") (pintype "passive"))
      (node (ref "C28") (pin "2") (pinfunction "2_2") (pintype "passive"))
      (node (ref "C29") (pin "2") (pinfunction "2_2") (pintype "passive"))
      (node (ref "C3") (pin "2") (pinfunction "2_2") (pintype "passive"))
      (node (ref "C31") (pin "2") (pinfunction "2_2") (pintype "passive"))
      (node (ref "C33") (pin "2") (pinfunction "2_2") (pintype "passive"))
      (node (ref "C34") (pin "2") (pinfunction "2_2") (pintype "passive"))
      (node (ref "C35") (pin "2") (pinfunction "2_2") (pintype "passive"))
      (node (ref "C36") (pin "2") (pinfunction "2_2") (pintype "passive"))
      (node (ref "C4") (pin "2") (pinfunction "2_2") (pintype "passive"))
      (node (ref "C41") (pin "C") (pinfunction "-_C") (pintype "passive"))
      (node (ref "C42") (pin "2") (pinfunction "2_2") (pintype "passive"))
      (node (ref "C43") (pin "1") (pinfunction "1_1") (pintype "passive"))
      (node (ref "C5") (pin "2") (pinfunction "2_2") (pintype "passive"))
      (node (ref "C6") (pin "1") (pinfunction "1_1") (pintype "passive"))
      (node (ref "C8") (pin "2") (pinfunction "2_2") (pintype "passive"))
      (node (ref "C9") (pin "2") (pinfunction "2_2") (pintype "passive"))
      (node (ref "D1") (pin "1") (pinfunction "K1_1") (pintype "passive"))
      (node (ref "FTDI") (pin "1") (pinfunction "1_1") (pintype "passive"))
      (node (ref "GFCI") (pin "1") (pinfunction "1_1") (pintype "passive"))
      (node (ref "I2C") (pin "1") (pinfunction "1_1") (pintype "passive"))
      (node (ref "IC1") (pin "5") (pinfunction "+IN_5") (pintype "input"))
      (node (ref "IC3") (pin "3") (pinfunction "+IN1_3") (pintype "input"))
      (node (ref "IC3") (pin "4") (pinfunction "GND_4") (pintype "power_in"))
      (node (ref "IC4") (pin "3") (pinfunction "GND_3") (pintype "bidirectional"))
      (node (ref "IC5") (pin "10") (pinfunction "VSS_10") (pintype "power_in"))
      (node (ref "IC5") (pin "15") (pinfunction "A0_15") (pintype "input"))
      (node (ref "IC5") (pin "16") (pinfunction "A1_16") (pintype "input"))
      (node (ref "IC5") (pin "17") (pinfunction "A2_17") (pintype "input"))
      (node (ref "IC7") (pin "P$1") (pinfunction "1_P$1") (pintype "bidirectional"))
      (node (ref "IC7") (pin "P$3") (pinfunction "3_P$3") (pintype "bidirectional"))
      (node (ref "IC7") (pin "P$4") (pinfunction "4_P$4") (pintype "bidirectional"))
      (node (ref "IC8") (pin "P$5") (pinfunction "GND_P$5") (pintype "bidirectional"))
      (node (ref "ISP1") (pin "6") (pinfunction "GND_6") (pintype "power_in"))
      (node (ref "LED") (pin "2") (pinfunction "2_2") (pintype "passive"))
      (node (ref "LED1") (pin "4") (pinfunction "GND_4") (pintype "power_in"))
      (node (ref "LED2") (pin "4") (pinfunction "GND_4") (pintype "power_in"))
      (node (ref "PS1") (pin "V-") (pinfunction "V-_V-") (pintype "bidirectional"))
      (node (ref "Q2") (pin "2") (pinfunction "E_2") (pintype "passive"))
      (node (ref "R15") (pin "2") (pinfunction "2_2") (pintype "passive"))
      (node (ref "R17") (pin "1") (pinfunction "1_1") (pintype "passive"))
      (node (ref "R19") (pin "2") (pinfunction "2_2") (pintype "passive"))
      (node (ref "R21") (pin "2") (pinfunction "2_2") (pintype "passive"))
      (node (ref "R6") (pin "2") (pinfunction "2_2") (pintype "passive"))
      (node (ref "R8") (pin "1") (pinfunction "1_1") (pintype "passive"))
      (node (ref "RESET") (pin "A") (pinfunction "P_A") (pintype "passive"))
      (node (ref "RESET") (pin "A'") (pinfunction "P1_A'") (pintype "passive"))
      (node (ref "SFQ") (pin "1") (pinfunction "1_1") (pintype "power_in"))
      (node (ref "SH1") (pin "2") (pinfunction "P$2_2") (pintype "bidirectional"))
      (node (ref "TEST_COIL") (pin "P$2") (pinfunction "P$2_P$2") (pintype "bidirectional"))
      (node (ref "TVS") (pin "A") (pinfunction "A_A") (pintype "passive"))
      (node (ref "U$9") (pin "P$1") (pinfunction "GND_P$1") (pintype "bidirectional"))
      (node (ref "U1") (pin "4") (pinfunction "GND_4") (pintype "bidirectional"))
      (node (ref "U2") (pin "4") (pinfunction "GND_4") (pintype "bidirectional"))
      (node (ref "X2") (pin "1") (pinfunction "GND_1") (pintype "passive"))
      (node (ref "X2") (pin "15") (pinfunction "GND_15") (pintype "passive"))
      (node (ref "X2") (pin "38") (pinfunction "GND_38") (pintype "passive"))
      (node (ref "X2") (pin "P$1") (pinfunction "GND_P$1") (pintype "passive"))
    )
    (net (code "50") (name "Net-(C14-+)") (class "Default")
      (node (ref "C14") (pin "A") (pinfunction "+_A") (pintype "passive"))
      (node (ref "C7") (pin "2") (pinfunction "2_2") (pintype "passive"))
      (node (ref "D3") (pin "C") (pinfunction "C_C") (pintype "passive"))
      (node (ref "R16") (pin "1") (pinfunction "1_1") (pintype "passive"))
      (node (ref "R18") (pin "2") (pinfunction "2_2") (pintype "passive"))
    )
    (net (code "51") (name "Net-(D1-K2)") (class "Default")
      (node (ref "D1") (pin "2") (pinfunction "K2_2") (pintype "passive"))
      (node (ref "GFCI") (pin "2") (pinfunction "2_2") (pintype "passive"))
      (node (ref "R17") (pin "2") (pinfunction "2_2") (pintype "passive"))
      (node (ref "R20") (pin "2") (pinfunction "2_2") (pintype "passive"))
    )
    (net (code "52") (name "Net-(D2-PadA)") (class "Default")
      (node (ref "D2") (pin "A") (pinfunction "A_A") (pintype "passive"))
      (node (ref "R28") (pin "1") (pinfunction "1_1") (pintype "passive"))
    )
    (net (code "53") (name "Net-(D7-PadA)") (class "Default")
      (node (ref "D7") (pin "A") (pinfunction "A_A") (pintype "passive"))
      (node (ref "R32") (pin "1") (pinfunction "1_1") (pintype "passive"))
    )
    (net (code "54") (name "Net-(D8-PadA)") (class "Default")
      (node (ref "D8") (pin "A") (pinfunction "A_A") (pintype "passive"))
      (node (ref "R34") (pin "1") (pinfunction "1_1") (pintype "passive"))
    )
    (net (code "55") (name "Net-(D9-PadA)") (class "Default")
      (node (ref "D9") (pin "A") (pinfunction "A_A") (pintype "passive"))
      (node (ref "R36") (pin "1") (pinfunction "1_1") (pintype "passive"))
    )
    (net (code "56") (name "Net-(D10-PadA)") (class "Default")
      (node (ref "D10") (pin "A") (pinfunction "A_A") (pintype "passive"))
      (node (ref "R38") (pin "1") (pinfunction "1_1") (pintype "passive"))
    )
    (net (code "57") (name "Net-(D11-K1)") (class "Default")
      (node (ref "AMP") (pin "2") (pinfunction "2_2") (pintype "passive"))
      (node (ref "C11") (pin "1") (pinfunction "1_1") (pintype "passive"))
      (node (ref "D11") (pin "1") (pinfunction "K1_1") (pintype "passive"))
      (node (ref "R21") (pin "1") (pinfunction "1_1") (pintype "passive"))
      (node (ref "R25") (pin "2") (pinfunction "2_2") (pintype "passive"))
      (node (ref "R26") (pin "1") (pinfunction "1_1") (pintype "passive"))
    )
    (net (code "58") (name "Net-(IC1A--IN)") (class "Default")
      (node (ref "C15") (pin "2") (pinfunction "2_2") (pintype "passive"))
      (node (ref "IC1") (pin "2") (pinfunction "-IN_2") (pintype "input"))
      (node (ref "R8") (pin "2") (pinfunction "2_2") (pintype "passive"))
      (node (ref "R9") (pin "2") (pinfunction "2_2") (pintype "passive"))
    )
    (net (code "59") (name "Net-(IC1A-OUT)") (class "Default")
      (node (ref "IC1") (pin "1") (pinfunction "OUT_1") (pintype "output"))
      (node (ref "R1") (pin "2") (pinfunction "2_2") (pintype "passive"))
    )
    (net (code "60") (name "Net-(IC1B--IN)") (class "Default")
      (node (ref "IC1") (pin "6") (pinfunction "-IN_6") (pintype "input"))
      (node (ref "IC1") (pin "7") (pinfunction "OUT_7") (pintype "output"))
    )
    (net (code "61") (name "Net-(IC1C-P$V-)") (class "Default")
      (node (ref "C26") (pin "2") (pinfunction "2_2") (pintype "passive"))
      (node (ref "C5") (pin "1") (pinfunction "1_1") (pintype "passive"))
      (node (ref "IC1") (pin "4") (pinfunction "P$V-_4") (pintype "bidirectional"))
      (node (ref "IC4") (pin "5") (pinfunction "VOUT_5") (pintype "bidirectional"))
    )
    (net (code "62") (name "Net-(IC2-PB6(XTAL1{slash}TOSC1))") (class "Default")
      (node (ref "C1") (pin "2") (pinfunction "2_2") (pintype "passive"))
      (node (ref "IC2") (pin "7") (pinfunction "PB6(XTAL1/TOSC1)_7") (pintype "bidirectional"))
      (node (ref "Q1") (pin "2") (pinfunction "X1_2") (pintype "bidirectional"))
    )
    (net (code "63") (name "Net-(IC2-PB7(XTAL2{slash}TOSC2))") (class "Default")
      (node (ref "C2") (pin "1") (pinfunction "1_1") (pintype "passive"))
      (node (ref "IC2") (pin "8") (pinfunction "PB7(XTAL2/TOSC2)_8") (pintype "bidirectional"))
      (node (ref "Q1") (pin "4") (pinfunction "X2_4") (pintype "bidirectional"))
    )
    (net (code "64") (name "Net-(IC2-PD1(TXD))") (class "Default")
      (node (ref "IC2") (pin "31") (pinfunction "PD1(TXD)_31") (pintype "bidirectional"))
      (node (ref "J1") (pin "2") (pinfunction "2_2") (pintype "passive"))
    )
    (net (code "65") (name "Net-(IC2-PD7(AIN1))") (class "Default")
      (node (ref "IC2") (pin "11") (pinfunction "PD7(AIN1)_11") (pintype "bidirectional"))
      (node (ref "R31") (pin "1") (pinfunction "1_1") (pintype "passive"))
    )
    (net (code "66") (name "Net-(IC3A--IN1)") (class "Default")
      (node (ref "C7") (pin "1") (pinfunction "1_1") (pintype "passive"))
      (node (ref "IC3") (pin "2") (pinfunction "-IN1_2") (pintype "input"))
      (node (ref "R16") (pin "2") (pinfunction "2_2") (pintype "passive"))
      (node (ref "R20") (pin "1") (pinfunction "1_1") (pintype "passive"))
    )
    (net (code "67") (name "Net-(IC3A-OUT1)") (class "Default")
      (node (ref "D3") (pin "A") (pinfunction "A_A") (pintype "passive"))
      (node (ref "IC3") (pin "1") (pinfunction "OUT1_1") (pintype "output"))
    )
    (net (code "68") (name "Net-(IC3B-+IN2)") (class "Default")
      (node (ref "IC3") (pin "5") (pinfunction "+IN2_5") (pintype "input"))
      (node (ref "R18") (pin "1") (pinfunction "1_1") (pintype "passive"))
    )
    (net (code "69") (name "Net-(IC3B--IN2)") (class "Default")
      (node (ref "C16") (pin "2") (pinfunction "2_2") (pintype "passive"))
      (node (ref "IC3") (pin "6") (pinfunction "-IN2_6") (pintype "input"))
      (node (ref "R14") (pin "2") (pinfunction "2_2") (pintype "passive"))
      (node (ref "R15") (pin "1") (pinfunction "1_1") (pintype "passive"))
    )
    (net (code "70") (name "Net-(IC3B-OUT2)") (class "Default")
      (node (ref "D4") (pin "A") (pinfunction "A_A") (pintype "passive"))
      (node (ref "IC3") (pin "7") (pinfunction "OUT2_7") (pintype "output"))
    )
    (net (code "71") (name "Net-(IC4-CAP+)") (class "Default")
      (node (ref "C13") (pin "2") (pinfunction "2_2") (pintype "passive"))
      (node (ref "IC4") (pin "2") (pinfunction "CAP+_2") (pintype "bidirectional"))
    )
    (net (code "72") (name "Net-(IC4-CAP-)") (class "Default")
      (node (ref "C13") (pin "1") (pinfunction "1_1") (pintype "passive"))
      (node (ref "IC4") (pin "4") (pinfunction "CAP-_4") (pintype "bidirectional"))
    )
    (net (code "73") (name "Net-(IC7-2)") (class "Default")
      (node (ref "IC7") (pin "P$2") (pinfunction "2_P$2") (pintype "bidirectional"))
      (node (ref "R29") (pin "1") (pinfunction "1_1") (pintype "passive"))
    )
    (net (code "74") (name "Net-(IC8-I1+)") (class "Default")
      (node (ref "D7") (pin "C") (pinfunction "C_C") (pintype "passive"))
      (node (ref "D8") (pin "C") (pinfunction "C_C") (pintype "passive"))
      (node (ref "IC8") (pin "P$1") (pinfunction "I1+_P$1") (pintype "bidirectional"))
    )
    (net (code "75") (name "Net-(IC8-I2+)") (class "Default")
      (node (ref "D10") (pin "C") (pinfunction "C_C") (pintype "passive"))
      (node (ref "D2") (pin "C") (pinfunction "C_C") (pintype "passive"))
      (node (ref "D9") (pin "C") (pinfunction "C_C") (pintype "passive"))
      (node (ref "IC8") (pin "P$4") (pinfunction "I2+_P$4") (pintype "bidirectional"))
    )
    (net (code "76") (name "Net-(L1-1)") (class "Default")
      (node (ref "C30") (pin "2") (pinfunction "2_2") (pintype "passive"))
      (node (ref "L1") (pin "P$1") (pinfunction "1_P$1") (pintype "passive"))
      (node (ref "U2") (pin "5") (pinfunction "SW_5") (pintype "bidirectional"))
    )
    (net (code "77") (name "Net-(L2-1)") (class "Default")
      (node (ref "C32") (pin "2") (pinfunction "2_2") (pintype "passive"))
      (node (ref "L2") (pin "P$1") (pinfunction "1_P$1") (pintype "passive"))
      (node (ref "U1") (pin "5") (pinfunction "SW_5") (pintype "bidirectional"))
    )
    (net (code "78") (name "Net-(L3-Pad2)") (class "Default")
      (node (ref "L3") (pin "2") (pinfunction "2_2") (pintype "passive"))
      (node (ref "R27") (pin "2") (pinfunction "2_2") (pintype "passive"))
    )
    (net (code "79") (name "Net-(LED1-DO)") (class "Default")
      (node (ref "LED1") (pin "3") (pinfunction "DO_3") (pintype "output"))
      (node (ref "LED2") (pin "1") (pinfunction "DI_1") (pintype "input"))
    )
    (net (code "80") (name "Net-(Q1-G1)") (class "Default")
      (node (ref "C1") (pin "1") (pinfunction "1_1") (pintype "passive"))
      (node (ref "C2") (pin "2") (pinfunction "2_2") (pintype "passive"))
      (node (ref "Q1") (pin "1") (pinfunction "G1_1") (pintype "power_in"))
      (node (ref "Q1") (pin "3") (pinfunction "G2_3") (pintype "power_in"))
      (node (ref "SH2") (pin "1") (pinfunction "P$1_1") (pintype "bidirectional"))
    )
    (net (code "81") (name "Net-(Q2-B)") (class "Default")
      (node (ref "Q2") (pin "1") (pinfunction "B_1") (pintype "passive"))
      (node (ref "R24") (pin "1") (pinfunction "1_1") (pintype "passive"))
    )
    (net (code "82") (name "Net-(Q2-C)") (class "Default")
      (node (ref "D5") (pin "A") (pinfunction "A_A") (pintype "passive"))
      (node (ref "DCRELAY") (pin "1") (pinfunction "1_1") (pintype "passive"))
      (node (ref "Q2") (pin "3") (pinfunction "C_3") (pintype "passive"))
    )
    (net (code "83") (name "Net-(R2-Pad1)") (class "Default")
      (node (ref "R2") (pin "1") (pinfunction "1_1") (pintype "passive"))
      (node (ref "RGB_LED") (pin "3") (pinfunction "3_3") (pintype "passive"))
    )
    (net (code "84") (name "Net-(R3-Pad1)") (class "Default")
      (node (ref "R3") (pin "1") (pinfunction "1_1") (pintype "passive"))
      (node (ref "RGB_LED") (pin "2") (pinfunction "2_2") (pintype "passive"))
    )
    (net (code "85") (name "Net-(R4-Pad1)") (class "Default")
      (node (ref "R4") (pin "1") (pinfunction "1_1") (pintype "passive"))
      (node (ref "RGB_LED") (pin "1") (pinfunction "1_1") (pintype "passive"))
    )
    (net (code "86") (name "Net-(R23-Pad2)") (class "Default")
      (node (ref "R23") (pin "2") (pinfunction "2_2") (pintype "passive"))
      (node (ref "TEST_COIL") (pin "P$1") (pinfunction "P$1_P$1") (pintype "bidirectional"))
    )
    (net (code "87") (name "Net-(R28-Pad2)") (class "Default")
      (node (ref "R28") (pin "2") (pinfunction "2_2") (pintype "passive"))
      (node (ref "R30") (pin "1") (pinfunction "1_1") (pintype "passive"))
    )
    (net (code "88") (name "Net-(R32-Pad2)") (class "Default")
      (node (ref "R32") (pin "2") (pinfunction "2_2") (pintype "passive"))
      (node (ref "R33") (pin "1") (pinfunction "1_1") (pintype "passive"))
    )
    (net (code "89") (name "Net-(R34-Pad2)") (class "Default")
      (node (ref "R34") (pin "2") (pinfunction "2_2") (pintype "passive"))
      (node (ref "R35") (pin "1") (pinfunction "1_1") (pintype "passive"))
    )
    (net (code "90") (name "Net-(R36-Pad2)") (class "Default")
      (node (ref "R36") (pin "2") (pinfunction "2_2") (pintype "passive"))
      (node (ref "R37") (pin "1") (pinfunction "1_1") (pintype "passive"))
    )
    (net (code "91") (name "Net-(R38-Pad2)") (class "Default")
      (node (ref "R38") (pin "2") (pinfunction "2_2") (pintype "passive"))
      (node (ref "R39") (pin "1") (pinfunction "1_1") (pintype "passive"))
    )
    (net (code "92") (name "Net-(U1-BST)") (class "Default")
      (node (ref "C32") (pin "1") (pinfunction "1_1") (pintype "passive"))
      (node (ref "U1") (pin "6") (pinfunction "BST_6") (pintype "bidirectional"))
    )
    (net (code "93") (name "Net-(U2-BST)") (class "Default")
      (node (ref "C30") (pin "1") (pinfunction "1_1") (pintype "passive"))
      (node (ref "U2") (pin "6") (pinfunction "BST_6") (pintype "bidirectional"))
    )
    (net (code "94") (name "PE") (class "Default")
      (node (ref "C37") (pin "P$1") (pinfunction "1_P$1") (pintype "passive"))
      (node (ref "G1") (pin "1") (pinfunction "1_1") (pintype "passive"))
      (node (ref "IC8") (pin "P$2") (pinfunction "I1-_P$2") (pintype "bidirectional"))
      (node (ref "IC8") (pin "P$3") (pinfunction "I2-_P$3") (pintype "bidirectional"))
      (node (ref "M3") (pin "P$1") (pinfunction "1_P$1") (pintype "passive"))
      (node (ref "M4") (pin "P$1") (pinfunction "1_P$1") (pintype "passive"))
      (node (ref "RF1") (pin "P$1") (pinfunction "1_P$1") (pintype "passive"))
      (node (ref "U$3") (pin "P$1") (pinfunction "GND_P$1") (pintype "bidirectional"))
    )
    (net (code "95") (name "unconnected-(D1-AA-Pad3)") (class "Default")
      (node (ref "D1") (pin "3") (pinfunction "AA_3") (pintype "passive"))
    )
    (net (code "96") (name "unconnected-(D11-AA-Pad3)") (class "Default")
      (node (ref "D11") (pin "3") (pinfunction "AA_3") (pintype "passive"))
    )
    (net (code "97") (name "unconnected-(FTDI-Pad2)") (class "Default")
      (node (ref "FTDI") (pin "2") (pinfunction "2_2") (pintype "passive"))
    )
    (net (code "98") (name "unconnected-(IC4-LV-Pad6)") (class "Default")
      (node (ref "IC4") (pin "6") (pinfunction "LV_6") (pintype "bidirectional"))
    )
    (net (code "99") (name "unconnected-(IC4-OSC-Pad7)") (class "Default")
      (node (ref "IC4") (pin "7") (pinfunction "OSC_7") (pintype "bidirectional"))
    )
    (net (code "100") (name "unconnected-(IC5-GPA0-Pad21)") (class "Default")
      (node (ref "IC5") (pin "21") (pinfunction "GPA0_21") (pintype "bidirectional"))
    )
    (net (code "101") (name "unconnected-(IC5-GPA1-Pad22)") (class "Default")
      (node (ref "IC5") (pin "22") (pinfunction "GPA1_22") (pintype "bidirectional"))
    )
    (net (code "102") (name "unconnected-(IC5-GPA2-Pad23)") (class "Default")
      (node (ref "IC5") (pin "23") (pinfunction "GPA2_23") (pintype "bidirectional"))
    )
    (net (code "103") (name "unconnected-(IC5-GPA3-Pad24)") (class "Default")
      (node (ref "IC5") (pin "24") (pinfunction "GPA3_24") (pintype "bidirectional"))
    )
    (net (code "104") (name "unconnected-(IC5-GPA4-Pad25)") (class "Default")
      (node (ref "IC5") (pin "25") (pinfunction "GPA4_25") (pintype "bidirectional"))
    )
    (net (code "105") (name "unconnected-(IC5-GPA5-Pad26)") (class "Default")
      (node (ref "IC5") (pin "26") (pinfunction "GPA5_26") (pintype "bidirectional"))
    )
    (net (code "106") (name "unconnected-(IC5-GPB1-Pad2)") (class "Default")
      (node (ref "IC5") (pin "2") (pinfunction "GPB1_2") (pintype "bidirectional"))
    )
    (net (code "107") (name "unconnected-(IC5-GPB2-Pad3)") (class "Default")
      (node (ref "IC5") (pin "3") (pinfunction "GPB2_3") (pintype "bidirectional"))
    )
    (net (code "108") (name "unconnected-(IC5-GPB3-Pad4)") (class "Default")
      (node (ref "IC5") (pin "4") (pinfunction "GPB3_4") (pintype "bidirectional"))
    )
    (net (code "109") (name "unconnected-(IC5-GPB4-Pad5)") (class "Default")
      (node (ref "IC5") (pin "5") (pinfunction "GPB4_5") (pintype "bidirectional"))
    )
    (net (code "110") (name "unconnected-(IC5-GPB5-Pad6)") (class "Default")
      (node (ref "IC5") (pin "6") (pinfunction "GPB5_6") (pintype "bidirectional"))
    )
    (net (code "111") (name "unconnected-(IC5-GPB6-Pad7)") (class "Default")
      (node (ref "IC5") (pin "7") (pinfunction "GPB6_7") (pintype "bidirectional"))
    )
    (net (code "112") (name "unconnected-(IC5-GPB7-Pad8)") (class "Default")
      (node (ref "IC5") (pin "8") (pinfunction "GPB7_8") (pintype "bidirectional"))
    )
    (net (code "113") (name "unconnected-(IC5-INTA-Pad20)") (class "Default")
      (node (ref "IC5") (pin "20") (pinfunction "INTA_20") (pintype "output"))
    )
    (net (code "114") (name "unconnected-(IC5-INTB-Pad19)") (class "Default")
      (node (ref "IC5") (pin "19") (pinfunction "INTB_19") (pintype "output"))
    )
    (net (code "115") (name "unconnected-(IC7-5-PadP$5)") (class "Default")
      (node (ref "IC7") (pin "P$5") (pinfunction "5_P$5") (pintype "bidirectional"))
    )
    (net (code "116") (name "unconnected-(U$25-1-PadP$1)") (class "Default")
      (node (ref "U$25") (pin "P$1") (pinfunction "1_P$1") (pintype "passive"))
    )
    (net (code "117") (name "unconnected-(U$25-2-PadP$2)") (class "Default")
      (node (ref "U$25") (pin "P$2") (pinfunction "2_P$2") (pintype "passive"))
    )
    (net (code "118") (name "unconnected-(U$25-4-PadP$4)") (class "Default")
      (node (ref "U$25") (pin "P$4") (pinfunction "4_P$4") (pintype "passive"))
    )
    (net (code "119") (name "unconnected-(X2-CLK-Pad20)") (class "Default")
      (node (ref "X2") (pin "20") (pinfunction "CLK_20") (pintype "bidirectional"))
    )
    (net (code "120") (name "unconnected-(X2-CMD-Pad19)") (class "Default")
      (node (ref "X2") (pin "19") (pinfunction "CMD_19") (pintype "bidirectional"))
    )
    (net (code "121") (name "unconnected-(X2-I34{slash}A1_6-Pad6)") (class "Default")
      (node (ref "X2") (pin "6") (pinfunction "I34/A1_6_6") (pintype "bidirectional"))
    )
    (net (code "122") (name "unconnected-(X2-I35{slash}A1_7-Pad7)") (class "Default")
      (node (ref "X2") (pin "7") (pinfunction "I35/A1_7_7") (pintype "bidirectional"))
    )
    (net (code "123") (name "unconnected-(X2-IO2{slash}A2_2-Pad24)") (class "Default")
      (node (ref "X2") (pin "24") (pinfunction "IO2/A2_2_24") (pintype "bidirectional"))
    )
    (net (code "124") (name "unconnected-(X2-IO4{slash}A2_0-Pad26)") (class "Default")
      (node (ref "X2") (pin "26") (pinfunction "IO4/A2_0_26") (pintype "bidirectional"))
    )
    (net (code "125") (name "unconnected-(X2-IO5-Pad29)") (class "Default")
      (node (ref "X2") (pin "29") (pinfunction "IO5_29") (pintype "bidirectional"))
    )
    (net (code "126") (name "unconnected-(X2-IO12{slash}A2_5-Pad14)") (class "Default")
      (node (ref "X2") (pin "14") (pinfunction "IO12/A2_5_14") (pintype "bidirectional"))
    )
    (net (code "127") (name "unconnected-(X2-IO13{slash}A2_4-Pad16)") (class "Default")
      (node (ref "X2") (pin "16") (pinfunction "IO13/A2_4_16") (pintype "bidirectional"))
    )
    (net (code "128") (name "unconnected-(X2-IO14{slash}A2_6-Pad13)") (class "Default")
      (node (ref "X2") (pin "13") (pinfunction "IO14/A2_6_13") (pintype "bidirectional"))
    )
    (net (code "129") (name "unconnected-(X2-IO15{slash}A2_3-Pad23)") (class "Default")
      (node (ref "X2") (pin "23") (pinfunction "IO15/A2_3_23") (pintype "bidirectional"))
    )
    (net (code "130") (name "unconnected-(X2-IO16-Pad27)") (class "Default")
      (node (ref "X2") (pin "27") (pinfunction "IO16_27") (pintype "bidirectional"))
    )
    (net (code "131") (name "unconnected-(X2-IO18-Pad30)") (class "Default")
      (node (ref "X2") (pin "30") (pinfunction "IO18_30") (pintype "bidirectional"))
    )
    (net (code "132") (name "unconnected-(X2-IO19-Pad31)") (class "Default")
      (node (ref "X2") (pin "31") (pinfunction "IO19_31") (pintype "bidirectional"))
    )
    (net (code "133") (name "unconnected-(X2-IO23-Pad37)") (class "Default")
      (node (ref "X2") (pin "37") (pinfunction "IO23_37") (pintype "bidirectional"))
    )
    (net (code "134") (name "unconnected-(X2-IO25{slash}DAC1{slash}A2_8-Pad10)") (class "Default")
      (node (ref "X2") (pin "10") (pinfunction "IO25/DAC1/A2_8_10") (pintype "bidirectional"))
    )
    (net (code "135") (name "unconnected-(X2-IO26{slash}DAC2{slash}A2_9-Pad11)") (class "Default")
      (node (ref "X2") (pin "11") (pinfunction "IO26/DAC2/A2_9_11") (pintype "bidirectional"))
    )
    (net (code "136") (name "unconnected-(X2-IO27{slash}A2_7-Pad12)") (class "Default")
      (node (ref "X2") (pin "12") (pinfunction "IO27/A2_7_12") (pintype "bidirectional"))
    )
    (net (code "137") (name "unconnected-(X2-IO32{slash}A1_4{slash}X32P-Pad8)") (class "Default")
      (node (ref "X2") (pin "8") (pinfunction "IO32/A1_4/X32P_8") (pintype "bidirectional"))
    )
    (net (code "138") (name "unconnected-(X2-IO33{slash}A1_5{slash}X32N-Pad9)") (class "Default")
      (node (ref "X2") (pin "9") (pinfunction "IO33/A1_5/X32N_9") (pintype "bidirectional"))
    )
    (net (code "139") (name "unconnected-(X2-IO36{slash}SEN_VP{slash}A1_0-Pad4)") (class "Default")
      (node (ref "X2") (pin "4") (pinfunction "IO36/SEN_VP/A1_0_4") (pintype "passive"))
    )
    (net (code "140") (name "unconnected-(X2-IO39{slash}SEN_VN{slash}A1_3-Pad5)") (class "Default")
      (node (ref "X2") (pin "5") (pinfunction "IO39/SEN_VN/A1_3_5") (pintype "passive"))
    )
    (net (code "141") (name "unconnected-(X2-SD0-Pad21)") (class "Default")
      (node (ref "X2") (pin "21") (pinfunction "SD0_21") (pintype "bidirectional"))
    )
    (net (code "142") (name "unconnected-(X2-SD1-Pad22)") (class "Default")
      (node (ref "X2") (pin "22") (pinfunction "SD1_22") (pintype "bidirectional"))
    )
    (net (code "143") (name "unconnected-(X2-SD2-Pad17)") (class "Default")
      (node (ref "X2") (pin "17") (pinfunction "SD2_17") (pintype "bidirectional"))
    )
    (net (code "144") (name "unconnected-(X2-SD3-Pad18)") (class "Default")
      (node (ref "X2") (pin "18") (pinfunction "SD3_18") (pintype "bidirectional"))
    )
  )
)
